# 2hz_timer.net
KiCad netlist of a schematic drawn in EAGLE
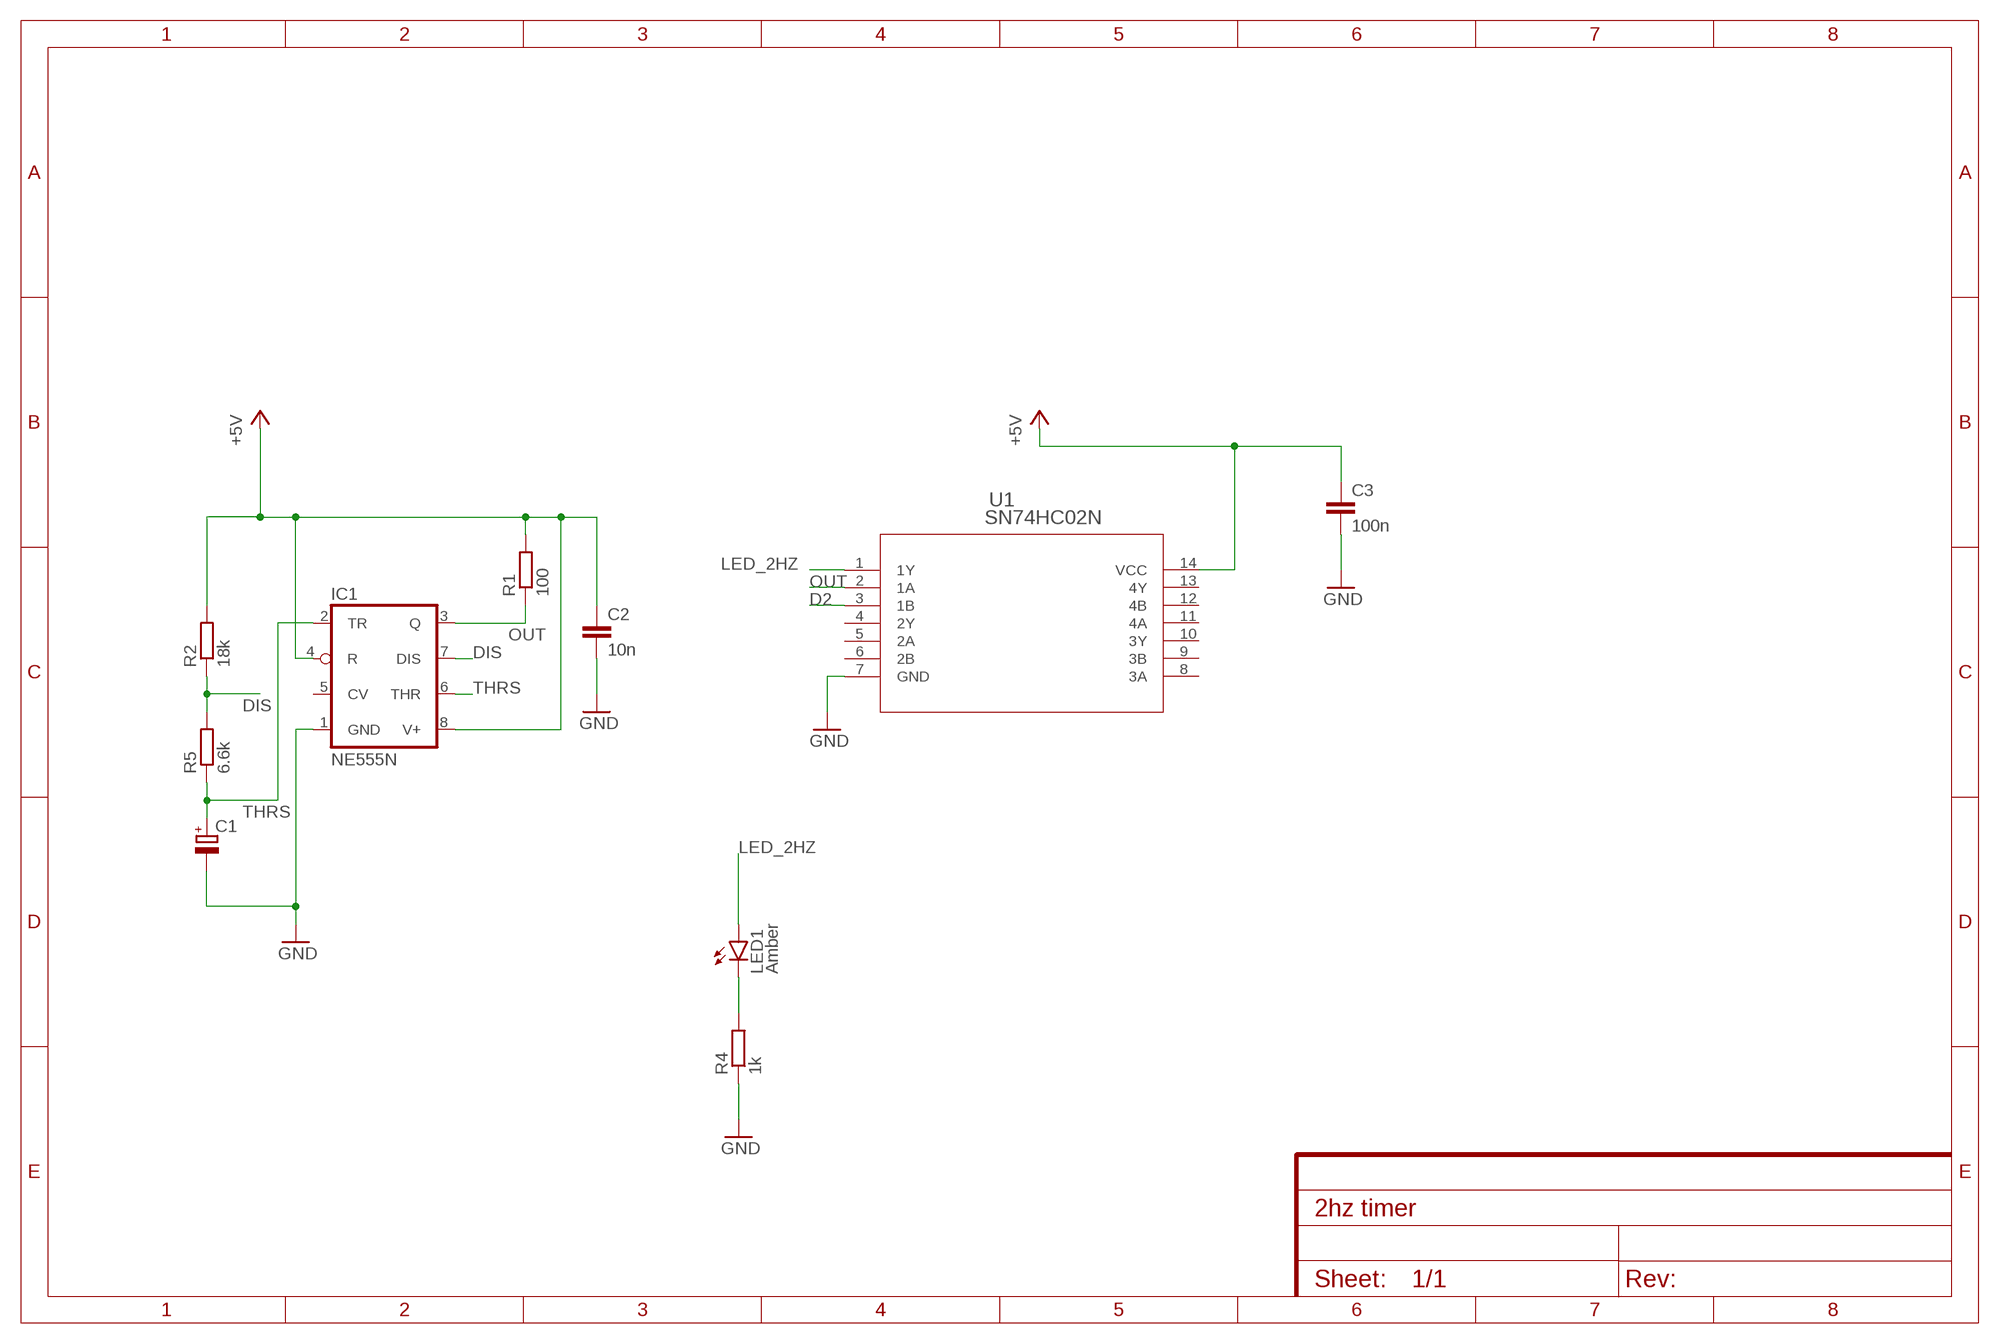
[diagram p0: schematic, sheet 1]

(export (version "E")
  (design (tool "Eeschema 10.0.6"))
  (components
    (comp (ref "C1")
      (value "CPOL-EUTT2D4")
      (footprint "eagle-import:TT2D4")
      (libsource (lib "eagle-import") (part "CPOL-EUTT2D4"))
    )
    (comp (ref "C2")
      (value "10n")
      (footprint "eagle-import:C025-024X044")
      (libsource (lib "eagle-import") (part "C-EU025-024X044"))
    )
    (comp (ref "C3")
      (value "100n")
      (footprint "eagle-import:C025-024X044")
      (libsource (lib "eagle-import") (part "C-EU025-024X044"))
    )
    (comp (ref "IC1")
      (value "NE555N")
      (footprint "eagle-import:DIL08-ROUND")
      (libsource (lib "eagle-import") (part "555NNE"))
    )
    (comp (ref "LED1")
      (value "Amber")
      (footprint "eagle-import:LED3MM")
      (libsource (lib "eagle-import") (part "LED_23MM"))
    )
    (comp (ref "R1")
      (value "100")
      (footprint "eagle-import:0204_7")
      (libsource (lib "eagle-import") (part "R-EU_0204/7"))
    )
    (comp (ref "R2")
      (value "18k")
      (footprint "eagle-import:0204_7")
      (libsource (lib "eagle-import") (part "R-EU_0204/7"))
    )
    (comp (ref "R4")
      (value "1k")
      (footprint "eagle-import:0204_7")
      (libsource (lib "eagle-import") (part "R-EU_0204/7"))
    )
    (comp (ref "R5")
      (value "6.6k")
      (footprint "eagle-import:0204_7")
      (libsource (lib "eagle-import") (part "R-EU_0204/7"))
    )
    (comp (ref "U1")
      (value "SN74HC02N")
      (footprint "eagle-import:N14")
      (fields (field (name "COPYRIGHT") "Copyright (C) 2023 Ultra Librarian. All rights reserved."))
      (libsource (lib "eagle-import") (part "SN74HC02N"))
    )
  )
  (nets
    (net (code "1") (name "+5V") (class "Default")
      (node (ref "C2") (pin "1") (pinfunction "1_1") (pintype "passive"))
      (node (ref "C3") (pin "1") (pinfunction "1_1") (pintype "passive"))
      (node (ref "IC1") (pin "4") (pinfunction "R_4") (pintype "input"))
      (node (ref "IC1") (pin "8") (pinfunction "V+_8") (pintype "power_in"))
      (node (ref "R1") (pin "2") (pinfunction "2_2") (pintype "passive"))
      (node (ref "R2") (pin "2") (pinfunction "2_2") (pintype "passive"))
      (node (ref "U1") (pin "14") (pinfunction "VCC_14") (pintype "power_in"))
    )
    (net (code "2") (name "/D2") (class "Default")
      (node (ref "U1") (pin "3") (pinfunction "1B_3") (pintype "input"))
    )
    (net (code "3") (name "/DIS") (class "Default")
      (node (ref "IC1") (pin "7") (pinfunction "DIS_7") (pintype "input"))
      (node (ref "R2") (pin "1") (pinfunction "1_1") (pintype "passive"))
      (node (ref "R5") (pin "2") (pinfunction "2_2") (pintype "passive"))
    )
    (net (code "4") (name "/LED_2HZ") (class "Default")
      (node (ref "LED1") (pin "A") (pinfunction "A_A") (pintype "passive"))
      (node (ref "U1") (pin "1") (pinfunction "1Y_1") (pintype "output"))
    )
    (net (code "5") (name "/OUT") (class "Default")
      (node (ref "IC1") (pin "3") (pinfunction "Q_3") (pintype "output"))
      (node (ref "R1") (pin "1") (pinfunction "1_1") (pintype "passive"))
      (node (ref "U1") (pin "2") (pinfunction "1A_2") (pintype "input"))
    )
    (net (code "6") (name "/THRS") (class "Default")
      (node (ref "C1") (pin "+") (pinfunction "+_+") (pintype "passive"))
      (node (ref "IC1") (pin "2") (pinfunction "TR_2") (pintype "input"))
      (node (ref "IC1") (pin "6") (pinfunction "THR_6") (pintype "input"))
      (node (ref "R5") (pin "1") (pinfunction "1_1") (pintype "passive"))
    )
    (net (code "7") (name "GND") (class "Default")
      (node (ref "C1") (pin "-") (pinfunction "-_-") (pintype "passive"))
      (node (ref "C2") (pin "2") (pinfunction "2_2") (pintype "passive"))
      (node (ref "C3") (pin "2") (pinfunction "2_2") (pintype "passive"))
      (node (ref "IC1") (pin "1") (pinfunction "GND_1") (pintype "power_in"))
      (node (ref "R4") (pin "1") (pinfunction "1_1") (pintype "passive"))
      (node (ref "U1") (pin "7") (pinfunction "GND_7") (pintype "power_in"))
    )
    (net (code "8") (name "Net-(LED1-C)") (class "Default")
      (node (ref "LED1") (pin "K") (pinfunction "C_K") (pintype "passive"))
      (node (ref "R4") (pin "2") (pinfunction "2_2") (pintype "passive"))
    )
    (net (code "9") (name "unconnected-(IC1-CV-Pad5)") (class "Default")
      (node (ref "IC1") (pin "5") (pinfunction "CV_5") (pintype "input"))
    )
    (net (code "10") (name "unconnected-(U1-2A-Pad5)") (class "Default")
      (node (ref "U1") (pin "5") (pinfunction "2A_5") (pintype "input"))
    )
    (net (code "11") (name "unconnected-(U1-2B-Pad6)") (class "Default")
      (node (ref "U1") (pin "6") (pinfunction "2B_6") (pintype "input"))
    )
    (net (code "12") (name "unconnected-(U1-2Y-Pad4)") (class "Default")
      (node (ref "U1") (pin "4") (pinfunction "2Y_4") (pintype "output"))
    )
    (net (code "13") (name "unconnected-(U1-3A-Pad8)") (class "Default")
      (node (ref "U1") (pin "8") (pinfunction "3A_8") (pintype "input"))
    )
    (net (code "14") (name "unconnected-(U1-3B-Pad9)") (class "Default")
      (node (ref "U1") (pin "9") (pinfunction "3B_9") (pintype "input"))
    )
    (net (code "15") (name "unconnected-(U1-3Y-Pad10)") (class "Default")
      (node (ref "U1") (pin "10") (pinfunction "3Y_10") (pintype "output"))
    )
    (net (code "16") (name "unconnected-(U1-4A-Pad11)") (class "Default")
      (node (ref "U1") (pin "11") (pinfunction "4A_11") (pintype "input"))
    )
    (net (code "17") (name "unconnected-(U1-4B-Pad12)") (class "Default")
      (node (ref "U1") (pin "12") (pinfunction "4B_12") (pintype "input"))
    )
    (net (code "18") (name "unconnected-(U1-4Y-Pad13)") (class "Default")
      (node (ref "U1") (pin "13") (pinfunction "4Y_13") (pintype "output"))
    )
  )
)
